# ProtoBIT.net
KiCad netlist of a schematic drawn in EAGLE
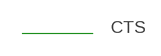
[diagram p0: schematic, sheet 1, part 1 of 2]
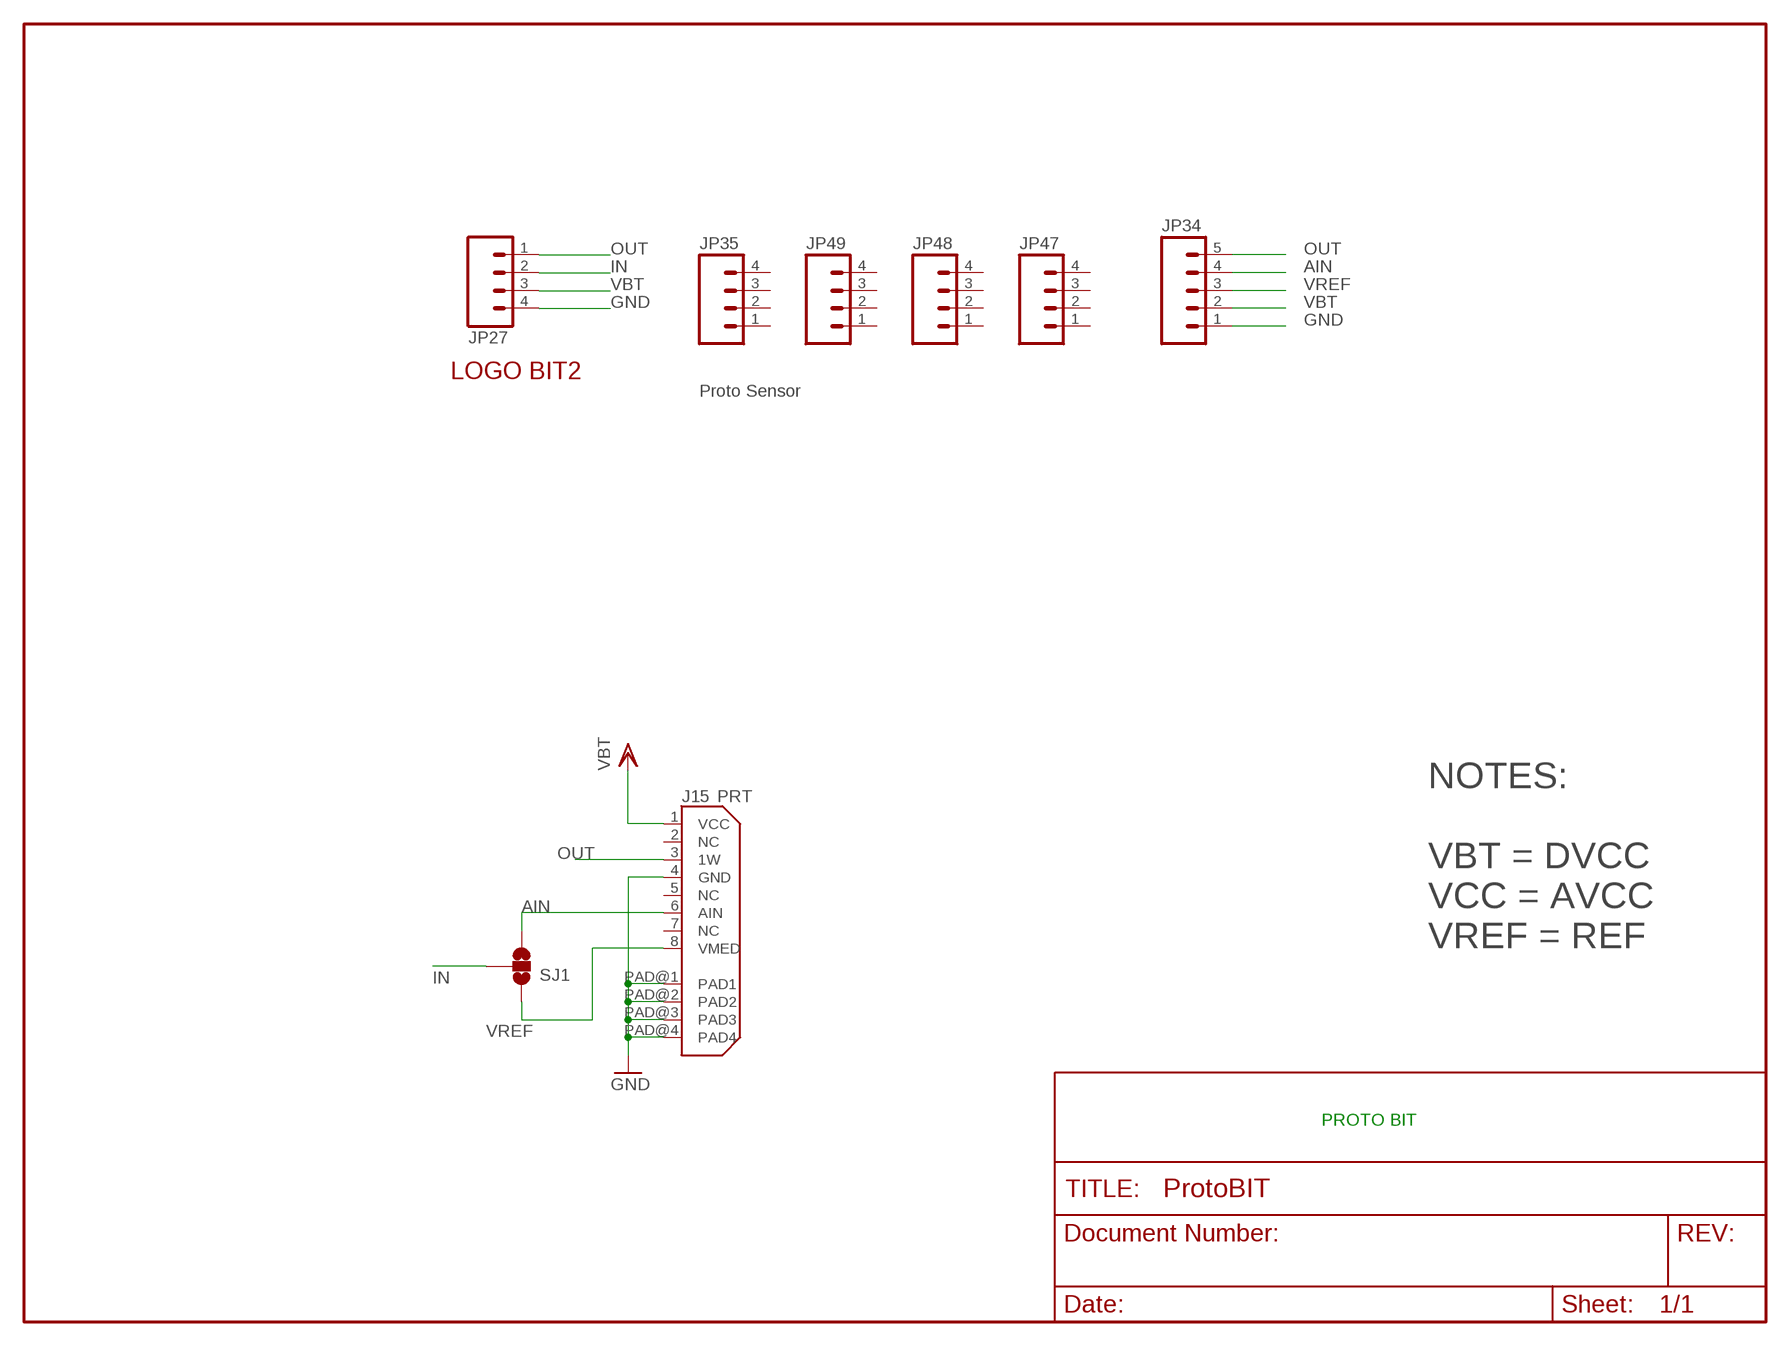
[diagram p1: schematic, sheet 1, part 2 of 2]

(export (version "E")
  (design (tool "Eeschema 10.0.6"))
  (components
    (comp (ref "J15")
      (value "PRT")
      (footprint "eagle-import:8PIN_MINI_USB_SINGLE_ROW_SMD")
      (libsource (lib "eagle-import") (part "ANALOG_CONN_COMTEK_8PINSMD"))
    )
    (comp (ref "JP27")
      (value "M04JST-PTH")
      (footprint "eagle-import:JST-4-PTH")
      (libsource (lib "eagle-import") (part "M04JST-PTH"))
    )
    (comp (ref "JP34")
      (value "M05")
      (footprint "eagle-import:JST-5-PTH-NO_SILK")
      (libsource (lib "eagle-import") (part "M05"))
    )
    (comp (ref "JP35")
      (value "M04PTH")
      (footprint "eagle-import:1X04")
      (libsource (lib "eagle-import") (part "SparkFun-Connectors_M04PTH"))
    )
    (comp (ref "JP47")
      (value "M04PTH")
      (footprint "eagle-import:1X04")
      (libsource (lib "eagle-import") (part "SparkFun-Connectors_M04PTH"))
    )
    (comp (ref "JP48")
      (value "M04PTH")
      (footprint "eagle-import:1X04")
      (libsource (lib "eagle-import") (part "SparkFun-Connectors_M04PTH"))
    )
    (comp (ref "JP49")
      (value "M04PTH")
      (footprint "eagle-import:1X04")
      (libsource (lib "eagle-import") (part "SparkFun-Connectors_M04PTH"))
    )
    (comp (ref "SJ1")
      (value "SOLDERJUMPER_2WAYS")
      (footprint "eagle-import:SJ_3")
      (libsource (lib "eagle-import") (part "SOLDERJUMPER_2WAYS"))
    )
    (comp (ref "U$14")
      (value "LOGO_BIT2(4.72X3.78)")
      (footprint "eagle-import:LOGO_BIT2")
      (libsource (lib "eagle-import") (part "LOGO_BIT2(4.72X3.78)"))
    )
  )
  (nets
    (net (code "1") (name "/AIN") (class "Default")
      (node (ref "J15") (pin "6") (pinfunction "AIN_6") (pintype "output"))
      (node (ref "JP34") (pin "4") (pinfunction "4_4") (pintype "passive"))
      (node (ref "SJ1") (pin "3") (pinfunction "3_3") (pintype "passive"))
    )
    (net (code "3") (name "/IN") (class "Default")
      (node (ref "JP27") (pin "2") (pinfunction "2_2") (pintype "passive"))
      (node (ref "SJ1") (pin "2") (pinfunction "2_2") (pintype "passive"))
    )
    (net (code "4") (name "/OUT") (class "Default")
      (node (ref "J15") (pin "3") (pinfunction "1W_3") (pintype "bidirectional"))
      (node (ref "JP27") (pin "1") (pinfunction "1_1") (pintype "passive"))
      (node (ref "JP34") (pin "5") (pinfunction "5_5") (pintype "passive"))
    )
    (net (code "5") (name "/VREF") (class "Default")
      (node (ref "J15") (pin "8") (pinfunction "VMED_8") (pintype "power_in"))
      (node (ref "JP34") (pin "3") (pinfunction "3_3") (pintype "passive"))
      (node (ref "SJ1") (pin "1") (pinfunction "1_1") (pintype "passive"))
    )
    (net (code "6") (name "GND") (class "Default")
      (node (ref "J15") (pin "4") (pinfunction "GND_4") (pintype "power_in"))
      (node (ref "J15") (pin "PAD@1") (pinfunction "PAD1_PAD@1") (pintype "power_in"))
      (node (ref "J15") (pin "PAD@2") (pinfunction "PAD2_PAD@2") (pintype "power_in"))
      (node (ref "J15") (pin "PAD@3") (pinfunction "PAD3_PAD@3") (pintype "power_in"))
      (node (ref "J15") (pin "PAD@4") (pinfunction "PAD4_PAD@4") (pintype "power_in"))
      (node (ref "JP27") (pin "4") (pinfunction "4_4") (pintype "passive"))
      (node (ref "JP34") (pin "1") (pinfunction "1_1") (pintype "passive"))
    )
    (net (code "7") (name "VBT") (class "Default")
      (node (ref "J15") (pin "1") (pinfunction "VCC_1") (pintype "power_in"))
      (node (ref "JP27") (pin "3") (pinfunction "3_3") (pintype "passive"))
      (node (ref "JP34") (pin "2") (pinfunction "2_2") (pintype "passive"))
    )
    (net (code "8") (name "unconnected-(J15-NC-Pad2)") (class "Default")
      (node (ref "J15") (pin "2") (pinfunction "NC_2") (pintype "no_connect"))
    )
    (net (code "9") (name "unconnected-(J15-NC-Pad5)") (class "Default")
      (node (ref "J15") (pin "5") (pinfunction "NC_5") (pintype "no_connect"))
    )
    (net (code "10") (name "unconnected-(J15-NC-Pad7)") (class "Default")
      (node (ref "J15") (pin "7") (pinfunction "NC_7") (pintype "no_connect"))
    )
    (net (code "11") (name "unconnected-(JP35-Pad1)") (class "Default")
      (node (ref "JP35") (pin "1") (pinfunction "1_1") (pintype "passive"))
    )
    (net (code "12") (name "unconnected-(JP35-Pad2)") (class "Default")
      (node (ref "JP35") (pin "2") (pinfunction "2_2") (pintype "passive"))
    )
    (net (code "13") (name "unconnected-(JP35-Pad3)") (class "Default")
      (node (ref "JP35") (pin "3") (pinfunction "3_3") (pintype "passive"))
    )
    (net (code "14") (name "unconnected-(JP35-Pad4)") (class "Default")
      (node (ref "JP35") (pin "4") (pinfunction "4_4") (pintype "passive"))
    )
    (net (code "15") (name "unconnected-(JP47-Pad1)") (class "Default")
      (node (ref "JP47") (pin "1") (pinfunction "1_1") (pintype "passive"))
    )
    (net (code "16") (name "unconnected-(JP47-Pad2)") (class "Default")
      (node (ref "JP47") (pin "2") (pinfunction "2_2") (pintype "passive"))
    )
    (net (code "17") (name "unconnected-(JP47-Pad3)") (class "Default")
      (node (ref "JP47") (pin "3") (pinfunction "3_3") (pintype "passive"))
    )
    (net (code "18") (name "unconnected-(JP47-Pad4)") (class "Default")
      (node (ref "JP47") (pin "4") (pinfunction "4_4") (pintype "passive"))
    )
    (net (code "19") (name "unconnected-(JP48-Pad1)") (class "Default")
      (node (ref "JP48") (pin "1") (pinfunction "1_1") (pintype "passive"))
    )
    (net (code "20") (name "unconnected-(JP48-Pad2)") (class "Default")
      (node (ref "JP48") (pin "2") (pinfunction "2_2") (pintype "passive"))
    )
    (net (code "21") (name "unconnected-(JP48-Pad3)") (class "Default")
      (node (ref "JP48") (pin "3") (pinfunction "3_3") (pintype "passive"))
    )
    (net (code "22") (name "unconnected-(JP48-Pad4)") (class "Default")
      (node (ref "JP48") (pin "4") (pinfunction "4_4") (pintype "passive"))
    )
    (net (code "23") (name "unconnected-(JP49-Pad1)") (class "Default")
      (node (ref "JP49") (pin "1") (pinfunction "1_1") (pintype "passive"))
    )
    (net (code "24") (name "unconnected-(JP49-Pad2)") (class "Default")
      (node (ref "JP49") (pin "2") (pinfunction "2_2") (pintype "passive"))
    )
    (net (code "25") (name "unconnected-(JP49-Pad3)") (class "Default")
      (node (ref "JP49") (pin "3") (pinfunction "3_3") (pintype "passive"))
    )
    (net (code "26") (name "unconnected-(JP49-Pad4)") (class "Default")
      (node (ref "JP49") (pin "4") (pinfunction "4_4") (pintype "passive"))
    )
  )
)
